# eps_bt2.net
KiCad netlist of a schematic drawn in Altium Designer
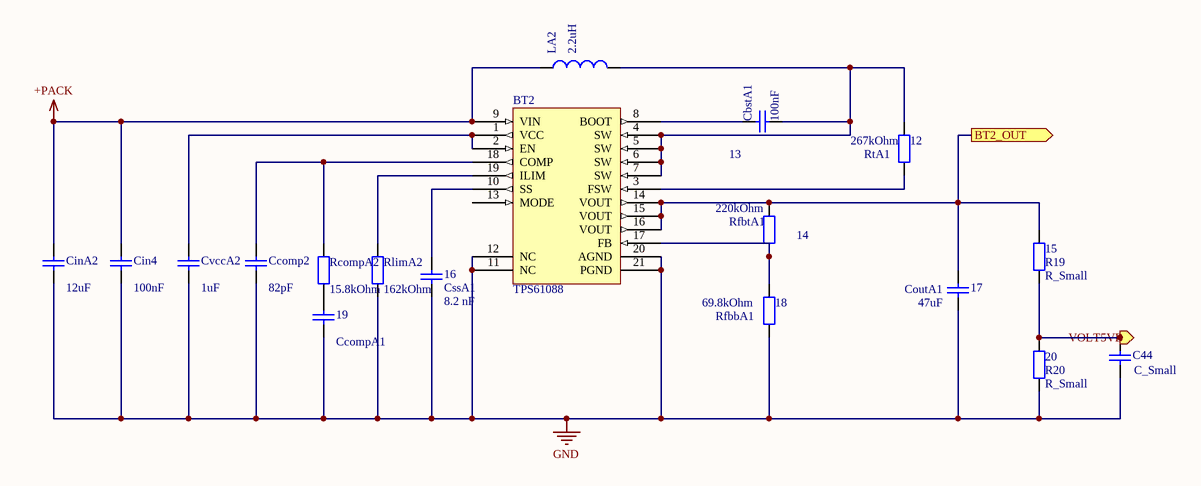
[diagram p0: eps_bt2.SchDoc]

(export (version "E")
  (design (tool "Eeschema 10.0.6"))
  (components
    (comp (ref "12")
      (value "RtA1")
      (footprint "1608[0603]")
      (description "Resistor")
      (fields (field (name "ALTIUM_VALUE") "267kOhm") (field (name "PUBLISHER") "Altium Limited"))
      (libsource (lib "") (part "Res2_1"))
    )
    (comp (ref "13")
      (value "CbstA1")
      (footprint "1608[0603]")
      (description "Capacitor")
      (fields (field (name "ALTIUM_VALUE") "100nF") (field (name "PUBLISHER") "Altium Limited"))
      (libsource (lib "Miscellaneous Devices") (part "Cap"))
    )
    (comp (ref "14")
      (value "RfbtA1")
      (footprint "1608[0603]")
      (description "Resistor")
      (fields (field (name "ALTIUM_VALUE") "220kOhm") (field (name "PUBLISHER") "Altium Limited"))
      (libsource (lib "Miscellaneous Devices") (part "Res2"))
    )
    (comp (ref "15")
      (value "R19")
      (footprint "1608[0603]")
      (description "Resistor")
      (fields (field (name "ALTIUM_VALUE") "R_Small") (field (name "PUBLISHER") "Altium Limited"))
      (libsource (lib "Miscellaneous Devices") (part "Res2"))
    )
    (comp (ref "16")
      (value "CssA1")
      (footprint "1608[0603]")
      (description "Capacitor")
      (fields (field (name "ALTIUM_VALUE") "8.2 nF") (field (name "PUBLISHER") "Altium Limited"))
      (libsource (lib "Miscellaneous Devices") (part "Cap"))
    )
    (comp (ref "17")
      (value "CoutA1")
      (footprint "1608[0603]")
      (description "Capacitor")
      (fields (field (name "ALTIUM_VALUE") "47uF") (field (name "PUBLISHER") "Altium Limited"))
      (libsource (lib "Miscellaneous Devices") (part "Cap"))
    )
    (comp (ref "18")
      (value "RfbbA1")
      (footprint "1608[0603]")
      (description "Resistor")
      (fields (field (name "ALTIUM_VALUE") "69.8kOhm") (field (name "PUBLISHER") "Altium Limited"))
      (libsource (lib "Miscellaneous Devices") (part "Res2"))
    )
    (comp (ref "19")
      (value "CcompA1")
      (footprint "1608[0603]")
      (description "Capacitor")
      (fields (field (name "PUBLISHER") "Altium Limited"))
      (libsource (lib "Miscellaneous Devices") (part "Cap"))
    )
    (comp (ref "20")
      (value "R20")
      (footprint "1608[0603]")
      (description "Resistor")
      (fields (field (name "ALTIUM_VALUE") "R_Small") (field (name "PUBLISHER") "Altium Limited"))
      (libsource (lib "Miscellaneous Devices") (part "Res2"))
    )
    (comp (ref "BT2")
      (value "TPS61088")
      (footprint "QFN50P450X350X100-21N")
      (description "Boost converter")
      (libsource (lib "heron-general") (part "TPS61088"))
    )
    (comp (ref "C44")
      (value "C_Small")
      (footprint "1608[0603]")
      (description "Capacitor")
      (fields (field (name "PUBLISHER") "Altium Limited"))
      (libsource (lib "Miscellaneous Devices") (part "Cap"))
    )
    (comp (ref "Ccomp2")
      (value "82pF")
      (footprint "1608[0603]")
      (description "Capacitor")
      (fields (field (name "PUBLISHER") "Altium Limited"))
      (libsource (lib "Miscellaneous Devices") (part "Cap"))
    )
    (comp (ref "Cin4")
      (value "100nF")
      (footprint "1608[0603]")
      (description "Capacitor")
      (fields (field (name "PUBLISHER") "Altium Limited"))
      (libsource (lib "Miscellaneous Devices") (part "Cap"))
    )
    (comp (ref "CinA2")
      (value "12uF")
      (footprint "1608[0603]")
      (description "Capacitor")
      (fields (field (name "PUBLISHER") "Altium Limited"))
      (libsource (lib "Miscellaneous Devices") (part "Cap"))
    )
    (comp (ref "CvccA2")
      (value "1uF")
      (footprint "1608[0603]")
      (description "Capacitor")
      (fields (field (name "PUBLISHER") "Altium Limited"))
      (libsource (lib "Miscellaneous Devices") (part "Cap"))
    )
    (comp (ref "LA2")
      (value "2.2uH")
      (footprint "1608[0603]")
      (description "Inductor")
      (fields (field (name "PUBLISHER") "Altium Limited"))
      (libsource (lib "Miscellaneous Devices") (part "Inductor"))
    )
    (comp (ref "RcompA2")
      (value "15.8kOhm")
      (footprint "1608[0603]")
      (description "Resistor")
      (fields (field (name "PUBLISHER") "Altium Limited"))
      (libsource (lib "Miscellaneous Devices") (part "Res2"))
    )
    (comp (ref "RlimA2")
      (value "162kOhm")
      (footprint "1608[0603]")
      (description "Resistor")
      (fields (field (name "PUBLISHER") "Altium Limited"))
      (libsource (lib "Miscellaneous Devices") (part "Res2"))
    )
  )
  (nets
    (net (code "1") (name "+PACK") (class "Default")
      (node (ref "BT2") (pin "9") (pinfunction "VIN_9") (pintype "input"))
      (node (ref "Cin4") (pin "2") (pinfunction "2_2") (pintype "passive"))
      (node (ref "CinA2") (pin "2") (pinfunction "2_2") (pintype "passive"))
      (node (ref "LA2") (pin "1") (pinfunction "1_1") (pintype "passive"))
    )
    (net (code "2") (name "/BT2_OUT") (class "Default")
      (node (ref "14") (pin "2") (pinfunction "2_2") (pintype "passive"))
      (node (ref "15") (pin "2") (pinfunction "2_2") (pintype "passive"))
      (node (ref "17") (pin "2") (pinfunction "2_2") (pintype "passive"))
      (node (ref "BT2") (pin "14") (pinfunction "VOUT_14") (pintype "output"))
      (node (ref "BT2") (pin "15") (pinfunction "VOUT_15") (pintype "output"))
      (node (ref "BT2") (pin "16") (pinfunction "VOUT_16") (pintype "output"))
    )
    (net (code "3") (name "/VOLT5VB") (class "Default")
      (node (ref "15") (pin "1") (pinfunction "1_1") (pintype "passive"))
      (node (ref "20") (pin "2") (pinfunction "2_2") (pintype "passive"))
      (node (ref "C44") (pin "1") (pinfunction "1_1") (pintype "passive"))
    )
    (net (code "4") (name "GND") (class "Default")
      (node (ref "16") (pin "1") (pinfunction "1_1") (pintype "passive"))
      (node (ref "17") (pin "1") (pinfunction "1_1") (pintype "passive"))
      (node (ref "18") (pin "1") (pinfunction "1_1") (pintype "passive"))
      (node (ref "19") (pin "1") (pinfunction "1_1") (pintype "passive"))
      (node (ref "20") (pin "1") (pinfunction "1_1") (pintype "passive"))
      (node (ref "BT2") (pin "11") (pinfunction "NC_11") (pintype "passive"))
      (node (ref "BT2") (pin "12") (pinfunction "NC_12") (pintype "passive"))
      (node (ref "BT2") (pin "20") (pinfunction "AGND_20") (pintype "power_in"))
      (node (ref "BT2") (pin "21") (pinfunction "PGND_21") (pintype "power_in"))
      (node (ref "C44") (pin "2") (pinfunction "2_2") (pintype "passive"))
      (node (ref "Ccomp2") (pin "1") (pinfunction "1_1") (pintype "passive"))
      (node (ref "Cin4") (pin "1") (pinfunction "1_1") (pintype "passive"))
      (node (ref "CinA2") (pin "1") (pinfunction "1_1") (pintype "passive"))
      (node (ref "CvccA2") (pin "1") (pinfunction "1_1") (pintype "passive"))
      (node (ref "RlimA2") (pin "1") (pinfunction "1_1") (pintype "passive"))
    )
    (net (code "5") (name "Net-(12-Pad1)") (class "Default")
      (node (ref "12") (pin "1") (pinfunction "1_1") (pintype "passive"))
      (node (ref "13") (pin "1") (pinfunction "1_1") (pintype "passive"))
      (node (ref "BT2") (pin "4") (pinfunction "SW_4") (pintype "input"))
      (node (ref "BT2") (pin "5") (pinfunction "SW_5") (pintype "input"))
      (node (ref "BT2") (pin "6") (pinfunction "SW_6") (pintype "input"))
      (node (ref "BT2") (pin "7") (pinfunction "SW_7") (pintype "input"))
      (node (ref "LA2") (pin "2") (pinfunction "2_2") (pintype "passive"))
    )
    (net (code "6") (name "Net-(19-Pad2)") (class "Default")
      (node (ref "19") (pin "2") (pinfunction "2_2") (pintype "passive"))
      (node (ref "RcompA2") (pin "1") (pinfunction "1_1") (pintype "passive"))
    )
    (net (code "7") (name "Net-(BT2-BOOT)") (class "Default")
      (node (ref "13") (pin "2") (pinfunction "2_2") (pintype "passive"))
      (node (ref "BT2") (pin "8") (pinfunction "BOOT_8") (pintype "output"))
    )
    (net (code "8") (name "Net-(BT2-COMP)") (class "Default")
      (node (ref "BT2") (pin "18") (pinfunction "COMP_18") (pintype "output"))
      (node (ref "Ccomp2") (pin "2") (pinfunction "2_2") (pintype "passive"))
      (node (ref "RcompA2") (pin "2") (pinfunction "2_2") (pintype "passive"))
    )
    (net (code "9") (name "Net-(BT2-EN)") (class "Default")
      (node (ref "BT2") (pin "1") (pinfunction "VCC_1") (pintype "output"))
      (node (ref "BT2") (pin "2") (pinfunction "EN_2") (pintype "input"))
      (node (ref "CvccA2") (pin "2") (pinfunction "2_2") (pintype "passive"))
    )
    (net (code "10") (name "Net-(BT2-FB)") (class "Default")
      (node (ref "14") (pin "1") (pinfunction "1_1") (pintype "passive"))
      (node (ref "18") (pin "2") (pinfunction "2_2") (pintype "passive"))
      (node (ref "BT2") (pin "17") (pinfunction "FB_17") (pintype "input"))
    )
    (net (code "11") (name "Net-(BT2-FSW)") (class "Default")
      (node (ref "12") (pin "2") (pinfunction "2_2") (pintype "passive"))
      (node (ref "BT2") (pin "3") (pinfunction "FSW_3") (pintype "input"))
    )
    (net (code "12") (name "Net-(BT2-ILIM)") (class "Default")
      (node (ref "BT2") (pin "19") (pinfunction "ILIM_19") (pintype "output"))
      (node (ref "RlimA2") (pin "2") (pinfunction "2_2") (pintype "passive"))
    )
    (net (code "13") (name "Net-(BT2-SS)") (class "Default")
      (node (ref "16") (pin "2") (pinfunction "2_2") (pintype "passive"))
      (node (ref "BT2") (pin "10") (pinfunction "SS_10") (pintype "output"))
    )
    (net (code "14") (name "unconnected-(BT2-MODE-Pad13)") (class "Default")
      (node (ref "BT2") (pin "13") (pinfunction "MODE_13") (pintype "input"))
    )
  )
)
